# JY_HW2_Sche.net
KiCad netlist of a schematic drawn in EAGLE
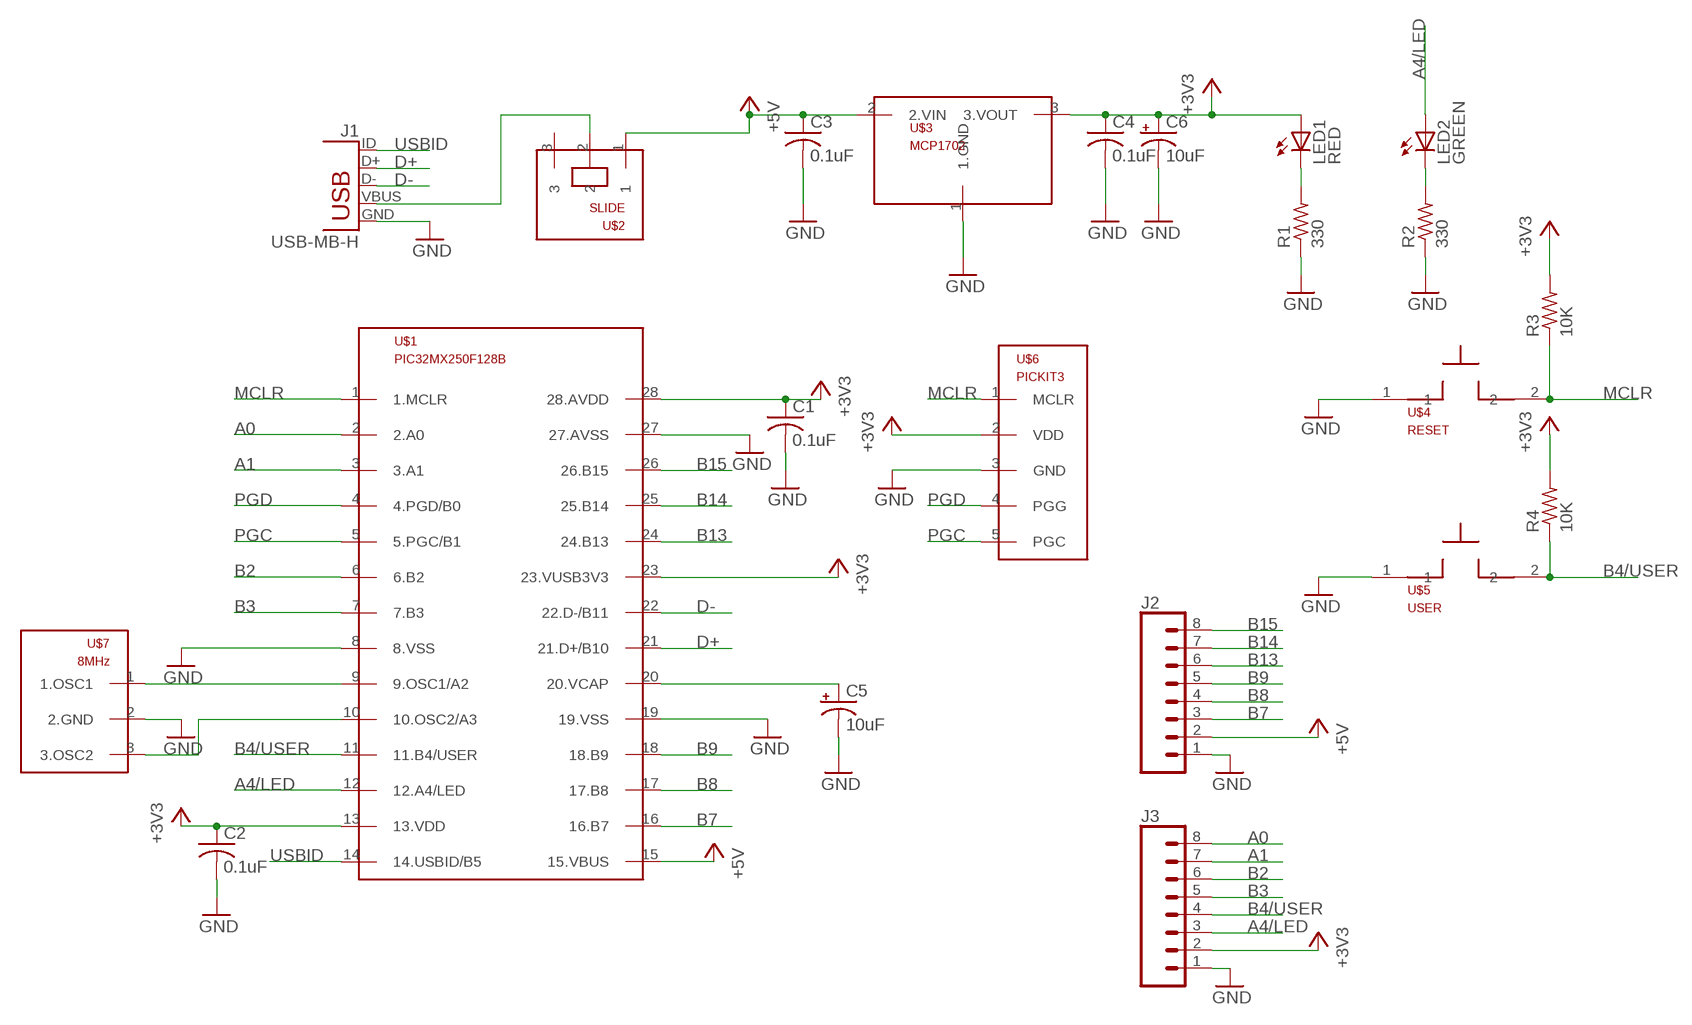
[diagram p0: schematic, sheet 1]

(export (version "E")
  (design (tool "Eeschema 10.0.6"))
  (components
    (comp (ref "C1")
      (value "0.1uF")
      (footprint "eagle-import:C025-025X050")
      (libsource (lib "eagle-import") (part "C-US025-025X050"))
    )
    (comp (ref "C2")
      (value "0.1uF")
      (footprint "eagle-import:C025-025X050")
      (libsource (lib "eagle-import") (part "C-US025-025X050"))
    )
    (comp (ref "C3")
      (value "0.1uF")
      (footprint "eagle-import:C025-025X050")
      (libsource (lib "eagle-import") (part "C-US025-025X050"))
    )
    (comp (ref "C4")
      (value "0.1uF")
      (footprint "eagle-import:C025-025X050")
      (libsource (lib "eagle-import") (part "C-US025-025X050"))
    )
    (comp (ref "C5")
      (value "10uF")
      (footprint "eagle-import:B45181B")
      (libsource (lib "eagle-import") (part "CPOL-USB45181B"))
    )
    (comp (ref "C6")
      (value "10uF")
      (footprint "eagle-import:B45181B")
      (libsource (lib "eagle-import") (part "CPOL-USB45181B"))
    )
    (comp (ref "J1")
      (value "USB-MB-H")
      (footprint "eagle-import:USB-MB-H")
      (libsource (lib "eagle-import") (part "USB-MB-H"))
    )
    (comp (ref "J2")
      (value "CONN_08\"")
      (footprint "eagle-import:1X08")
      (libsource (lib "eagle-import") (part "CONN_08{dblquote}"))
    )
    (comp (ref "J3")
      (value "CONN_08\"")
      (footprint "eagle-import:1X08")
      (libsource (lib "eagle-import") (part "CONN_08{dblquote}"))
    )
    (comp (ref "LED1")
      (value "RED")
      (footprint "eagle-import:LED3MM")
      (libsource (lib "eagle-import") (part "LED3MM"))
    )
    (comp (ref "LED2")
      (value "GREEN")
      (footprint "eagle-import:LED3MM")
      (libsource (lib "eagle-import") (part "LED3MM"))
    )
    (comp (ref "R1")
      (value "330")
      (footprint "eagle-import:0207_10")
      (libsource (lib "eagle-import") (part "R-US_0207/10"))
    )
    (comp (ref "R2")
      (value "330")
      (footprint "eagle-import:0207_10")
      (libsource (lib "eagle-import") (part "R-US_0207/10"))
    )
    (comp (ref "R3")
      (value "10K")
      (footprint "eagle-import:0207_10")
      (libsource (lib "eagle-import") (part "R-US_0207/10"))
    )
    (comp (ref "R4")
      (value "10K")
      (footprint "eagle-import:0207_10")
      (libsource (lib "eagle-import") (part "R-US_0207/10"))
    )
    (comp (ref "U$1")
      (value "PIC32MX250F128B")
      (footprint "eagle-import:DIL28-3")
      (libsource (lib "eagle-import") (part "PIC32MX250F128B"))
    )
    (comp (ref "U$2")
      (value "SLIDE")
      (footprint "eagle-import:SLIDE")
      (libsource (lib "eagle-import") (part "SLIDE"))
    )
    (comp (ref "U$3")
      (value "MCP1702")
      (footprint "eagle-import:TO92")
      (libsource (lib "eagle-import") (part "MCP1702"))
    )
    (comp (ref "U$4")
      (value "RESET")
      (footprint "eagle-import:PB")
      (libsource (lib "eagle-import") (part "PB"))
    )
    (comp (ref "U$5")
      (value "USER")
      (footprint "eagle-import:PB")
      (libsource (lib "eagle-import") (part "PB"))
    )
    (comp (ref "U$6")
      (value "PICKIT3")
      (footprint "eagle-import:1X05")
      (libsource (lib "eagle-import") (part "PICKIT3"))
    )
    (comp (ref "U$7")
      (value "8MHz")
      (footprint "eagle-import:OSC")
      (libsource (lib "eagle-import") (part "OSC"))
    )
  )
  (nets
    (net (code "1") (name "+3V3") (class "Default")
      (node (ref "C1") (pin "1") (pinfunction "1_1") (pintype "passive"))
      (node (ref "C2") (pin "1") (pinfunction "1_1") (pintype "passive"))
      (node (ref "C4") (pin "1") (pinfunction "1_1") (pintype "passive"))
      (node (ref "C6") (pin "+") (pinfunction "+_+") (pintype "passive"))
      (node (ref "J3") (pin "2") (pinfunction "2_2") (pintype "passive"))
      (node (ref "LED1") (pin "A") (pinfunction "A_A") (pintype "passive"))
      (node (ref "R3") (pin "2") (pinfunction "2_2") (pintype "passive"))
      (node (ref "R4") (pin "2") (pinfunction "2_2") (pintype "passive"))
      (node (ref "U$1") (pin "13") (pinfunction "13.VDD_13") (pintype "bidirectional"))
      (node (ref "U$1") (pin "23") (pinfunction "23.VUSB3V3_23") (pintype "bidirectional"))
      (node (ref "U$1") (pin "28") (pinfunction "28.AVDD_28") (pintype "bidirectional"))
      (node (ref "U$3") (pin "3") (pinfunction "3.VOUT_3") (pintype "bidirectional"))
      (node (ref "U$6") (pin "2") (pinfunction "VDD_2") (pintype "bidirectional"))
    )
    (net (code "2") (name "+5V") (class "Default")
      (node (ref "C3") (pin "1") (pinfunction "1_1") (pintype "passive"))
      (node (ref "J2") (pin "2") (pinfunction "2_2") (pintype "passive"))
      (node (ref "U$1") (pin "15") (pinfunction "15.VBUS_15") (pintype "bidirectional"))
      (node (ref "U$2") (pin "1") (pinfunction "1_1") (pintype "bidirectional"))
      (node (ref "U$3") (pin "2") (pinfunction "2.VIN_2") (pintype "bidirectional"))
    )
    (net (code "3") (name "/A0") (class "Default")
      (node (ref "J3") (pin "8") (pinfunction "8_8") (pintype "passive"))
      (node (ref "U$1") (pin "2") (pinfunction "2.A0_2") (pintype "bidirectional"))
    )
    (net (code "4") (name "/A1") (class "Default")
      (node (ref "J3") (pin "7") (pinfunction "7_7") (pintype "passive"))
      (node (ref "U$1") (pin "3") (pinfunction "3.A1_3") (pintype "bidirectional"))
    )
    (net (code "5") (name "/A4{slash}LED") (class "Default")
      (node (ref "J3") (pin "3") (pinfunction "3_3") (pintype "passive"))
      (node (ref "LED2") (pin "A") (pinfunction "A_A") (pintype "passive"))
      (node (ref "U$1") (pin "12") (pinfunction "12.A4/LED_12") (pintype "bidirectional"))
    )
    (net (code "6") (name "/B2") (class "Default")
      (node (ref "J3") (pin "6") (pinfunction "6_6") (pintype "passive"))
      (node (ref "U$1") (pin "6") (pinfunction "6.B2_6") (pintype "bidirectional"))
    )
    (net (code "7") (name "/B3") (class "Default")
      (node (ref "J3") (pin "5") (pinfunction "5_5") (pintype "passive"))
      (node (ref "U$1") (pin "7") (pinfunction "7.B3_7") (pintype "bidirectional"))
    )
    (net (code "8") (name "/B4{slash}USER") (class "Default")
      (node (ref "J3") (pin "4") (pinfunction "4_4") (pintype "passive"))
      (node (ref "R4") (pin "1") (pinfunction "1_1") (pintype "passive"))
      (node (ref "U$1") (pin "11") (pinfunction "11.B4/USER_11") (pintype "bidirectional"))
      (node (ref "U$5") (pin "2") (pinfunction "2_2") (pintype "bidirectional"))
    )
    (net (code "9") (name "/B7") (class "Default")
      (node (ref "J2") (pin "3") (pinfunction "3_3") (pintype "passive"))
      (node (ref "U$1") (pin "16") (pinfunction "16.B7_16") (pintype "bidirectional"))
    )
    (net (code "10") (name "/B8") (class "Default")
      (node (ref "J2") (pin "4") (pinfunction "4_4") (pintype "passive"))
      (node (ref "U$1") (pin "17") (pinfunction "17.B8_17") (pintype "bidirectional"))
    )
    (net (code "11") (name "/B9") (class "Default")
      (node (ref "J2") (pin "5") (pinfunction "5_5") (pintype "passive"))
      (node (ref "U$1") (pin "18") (pinfunction "18.B9_18") (pintype "bidirectional"))
    )
    (net (code "12") (name "/B13") (class "Default")
      (node (ref "J2") (pin "6") (pinfunction "6_6") (pintype "passive"))
      (node (ref "U$1") (pin "24") (pinfunction "24.B13_24") (pintype "bidirectional"))
    )
    (net (code "13") (name "/B14") (class "Default")
      (node (ref "J2") (pin "7") (pinfunction "7_7") (pintype "passive"))
      (node (ref "U$1") (pin "25") (pinfunction "25.B14_25") (pintype "bidirectional"))
    )
    (net (code "14") (name "/B15") (class "Default")
      (node (ref "J2") (pin "8") (pinfunction "8_8") (pintype "passive"))
      (node (ref "U$1") (pin "26") (pinfunction "26.B15_26") (pintype "bidirectional"))
    )
    (net (code "15") (name "/D+") (class "Default")
      (node (ref "J1") (pin "D+") (pinfunction "D+_D+") (pintype "bidirectional"))
      (node (ref "U$1") (pin "21") (pinfunction "21.D+/B10_21") (pintype "bidirectional"))
    )
    (net (code "16") (name "/D-") (class "Default")
      (node (ref "J1") (pin "D-") (pinfunction "D-_D-") (pintype "bidirectional"))
      (node (ref "U$1") (pin "22") (pinfunction "22.D-/B11_22") (pintype "bidirectional"))
    )
    (net (code "17") (name "/MCLR") (class "Default")
      (node (ref "R3") (pin "1") (pinfunction "1_1") (pintype "passive"))
      (node (ref "U$1") (pin "1") (pinfunction "1.MCLR_1") (pintype "bidirectional"))
      (node (ref "U$4") (pin "2") (pinfunction "2_2") (pintype "bidirectional"))
      (node (ref "U$6") (pin "1") (pinfunction "MCLR_1") (pintype "bidirectional"))
    )
    (net (code "18") (name "/PGC") (class "Default")
      (node (ref "U$1") (pin "5") (pinfunction "5.PGC/B1_5") (pintype "bidirectional"))
      (node (ref "U$6") (pin "5") (pinfunction "PGC_5") (pintype "bidirectional"))
    )
    (net (code "19") (name "/PGD") (class "Default")
      (node (ref "U$1") (pin "4") (pinfunction "4.PGD/B0_4") (pintype "bidirectional"))
      (node (ref "U$6") (pin "4") (pinfunction "PGG_4") (pintype "bidirectional"))
    )
    (net (code "20") (name "/USBID") (class "Default")
      (node (ref "J1") (pin "ID") (pinfunction "ID_ID") (pintype "bidirectional"))
      (node (ref "U$1") (pin "14") (pinfunction "14.USBID/B5_14") (pintype "bidirectional"))
    )
    (net (code "21") (name "GND") (class "Default")
      (node (ref "C1") (pin "2") (pinfunction "2_2") (pintype "passive"))
      (node (ref "C2") (pin "2") (pinfunction "2_2") (pintype "passive"))
      (node (ref "C3") (pin "2") (pinfunction "2_2") (pintype "passive"))
      (node (ref "C4") (pin "2") (pinfunction "2_2") (pintype "passive"))
      (node (ref "C5") (pin "-") (pinfunction "-_-") (pintype "passive"))
      (node (ref "C6") (pin "-") (pinfunction "-_-") (pintype "passive"))
      (node (ref "J1") (pin "GND") (pinfunction "GND_GND") (pintype "bidirectional"))
      (node (ref "J2") (pin "1") (pinfunction "1_1") (pintype "passive"))
      (node (ref "J3") (pin "1") (pinfunction "1_1") (pintype "passive"))
      (node (ref "R1") (pin "1") (pinfunction "1_1") (pintype "passive"))
      (node (ref "R2") (pin "1") (pinfunction "1_1") (pintype "passive"))
      (node (ref "U$1") (pin "19") (pinfunction "19.VSS_19") (pintype "bidirectional"))
      (node (ref "U$1") (pin "27") (pinfunction "27.AVSS_27") (pintype "bidirectional"))
      (node (ref "U$1") (pin "8") (pinfunction "8.VSS_8") (pintype "bidirectional"))
      (node (ref "U$3") (pin "1") (pinfunction "1.GND_1") (pintype "bidirectional"))
      (node (ref "U$4") (pin "1") (pinfunction "1_1") (pintype "bidirectional"))
      (node (ref "U$5") (pin "1") (pinfunction "1_1") (pintype "bidirectional"))
      (node (ref "U$6") (pin "3") (pinfunction "GND_3") (pintype "bidirectional"))
      (node (ref "U$7") (pin "2") (pinfunction "2.GND_2") (pintype "bidirectional"))
    )
    (net (code "22") (name "Net-(J1-PadVBUS)") (class "Default")
      (node (ref "J1") (pin "VBUS") (pinfunction "VBUS_VBUS") (pintype "bidirectional"))
      (node (ref "U$2") (pin "2") (pinfunction "2_2") (pintype "bidirectional"))
    )
    (net (code "23") (name "Net-(LED1-C)") (class "Default")
      (node (ref "LED1") (pin "K") (pinfunction "C_K") (pintype "passive"))
      (node (ref "R1") (pin "2") (pinfunction "2_2") (pintype "passive"))
    )
    (net (code "24") (name "Net-(LED2-C)") (class "Default")
      (node (ref "LED2") (pin "K") (pinfunction "C_K") (pintype "passive"))
      (node (ref "R2") (pin "2") (pinfunction "2_2") (pintype "passive"))
    )
    (net (code "25") (name "Net-(U$1-9.OSC1{slash}A2)") (class "Default")
      (node (ref "U$1") (pin "9") (pinfunction "9.OSC1/A2_9") (pintype "bidirectional"))
      (node (ref "U$7") (pin "1") (pinfunction "1.OSC1_1") (pintype "bidirectional"))
    )
    (net (code "26") (name "Net-(U$1-10.OSC2{slash}A3)") (class "Default")
      (node (ref "U$1") (pin "10") (pinfunction "10.OSC2/A3_10") (pintype "bidirectional"))
      (node (ref "U$7") (pin "3") (pinfunction "3.OSC2_3") (pintype "bidirectional"))
    )
    (net (code "27") (name "Net-(U$1-20.VCAP)") (class "Default")
      (node (ref "C5") (pin "+") (pinfunction "+_+") (pintype "passive"))
      (node (ref "U$1") (pin "20") (pinfunction "20.VCAP_20") (pintype "bidirectional"))
    )
    (net (code "28") (name "unconnected-(U$2-Pad3)") (class "Default")
      (node (ref "U$2") (pin "3") (pinfunction "3_3") (pintype "bidirectional"))
    )
  )
)
